# rm.net
KiCad netlist of a schematic drawn in EasyEDA Pro
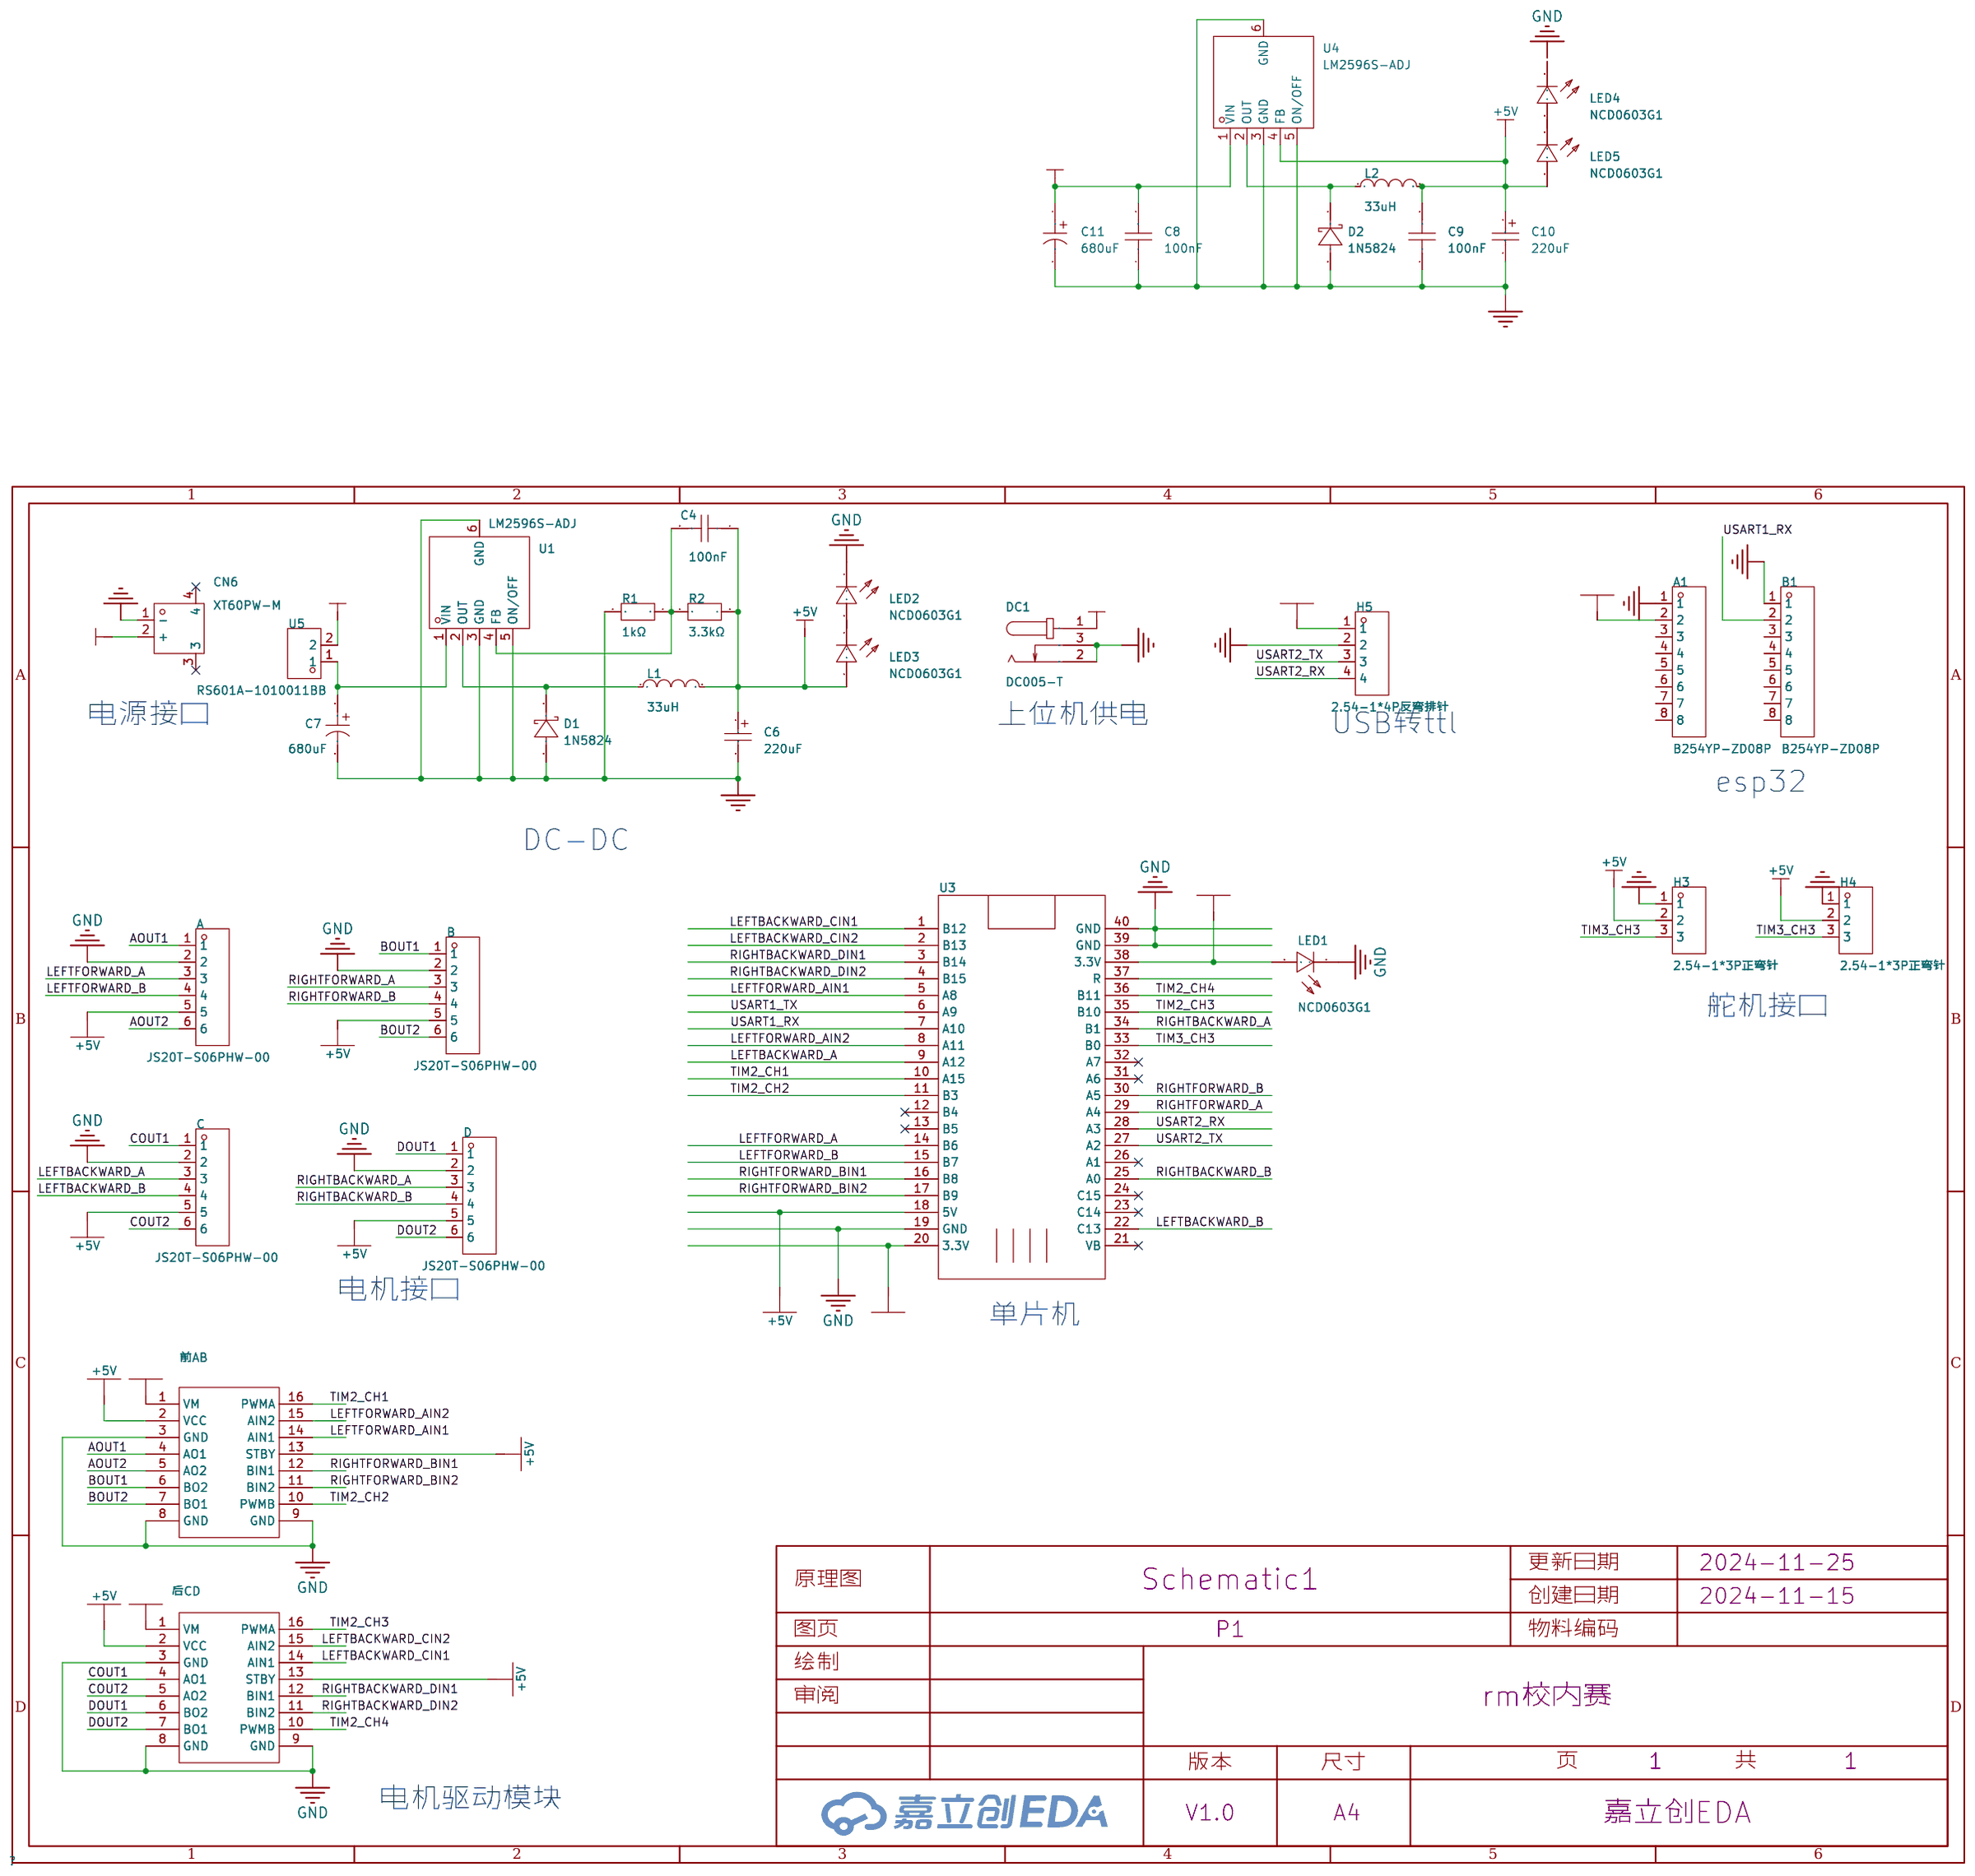
[diagram p0: schematic sheet]

(export (version "E")
  (design (tool "Eeschema 10.0.6"))
  (components
    (comp (ref "A")
      (value "JS20T-S06PHW-00")
      (footprint "easyedapro:CONN-TH_6P-P2.00_JS20T-S06PHW-00")
      (description "插针结构:1x6P;间距:2mm;安装方式:弯插;参考系列:PH;总PIN数:6P;排数:1;每排PIN数:6;触头材质:黄铜;")
      (fields (field (name "Manufacturer") "JS(钜硕电子)"))
      (libsource (lib "easyedapro") (part "JS20T-S06PHW-00"))
    )
    (comp (ref "A1")
      (value "B254YP-ZD08P")
      (footprint "easyedapro:HDR-TH_8P-P2.54-V-F")
      (fields (field (name "Manufacturer") "BXCONN(宝讯)"))
      (libsource (lib "easyedapro") (part "B254YP-ZD08P"))
    )
    (comp (ref "B")
      (value "JS20T-S06PHW-00")
      (footprint "easyedapro:CONN-TH_6P-P2.00_JS20T-S06PHW-00")
      (description "插针结构:1x6P;间距:2mm;安装方式:弯插;参考系列:PH;总PIN数:6P;排数:1;每排PIN数:6;触头材质:黄铜;")
      (fields (field (name "Manufacturer") "JS(钜硕电子)"))
      (libsource (lib "easyedapro") (part "JS20T-S06PHW-00"))
    )
    (comp (ref "B1")
      (value "B254YP-ZD08P")
      (footprint "easyedapro:HDR-TH_8P-P2.54-V-F")
      (fields (field (name "Manufacturer") "BXCONN(宝讯)"))
      (libsource (lib "easyedapro") (part "B254YP-ZD08P"))
    )
    (comp (ref "C")
      (value "JS20T-S06PHW-00")
      (footprint "easyedapro:CONN-TH_6P-P2.00_JS20T-S06PHW-00")
      (description "插针结构:1x6P;间距:2mm;安装方式:弯插;参考系列:PH;总PIN数:6P;排数:1;每排PIN数:6;触头材质:黄铜;")
      (fields (field (name "Manufacturer") "JS(钜硕电子)"))
      (libsource (lib "easyedapro") (part "JS20T-S06PHW-00"))
    )
    (comp (ref "C4")
      (value "100nF")
      (footprint "easyedapro:C0603")
      (description "容值:100nF;精度:±10%;额定电压:50V;材质(温度系数):X8L;")
      (fields (field (name "Manufacturer Part") "06035L104K4T2A") (field (name "Manufacturer") "Kyocera AVX"))
      (libsource (lib "easyedapro") (part "06035L104K4T2A"))
    )
    (comp (ref "C6")
      (value "220uF")
      (footprint "easyedapro:CASE-B_3528")
      (description "容值:220uF;精度:±20%;额定电压:6.3V;等效串联电阻:500mΩ@100kHz;")
      (fields
        (field (name "Manufacturer Part") "TLJB227M006R0500")
        (field (name "Manufacturer") "Kyocera AVX")
      )
      (libsource (lib "easyedapro") (part "TLJB227M006R0500"))
    )
    (comp (ref "C7")
      (value "680uF")
      (footprint "easyedapro:CAP-SMD_BD10.0-L10.3-W10.3-LS10.9-FD")
      (description "容值:680uF;精度:±20%;额定电压:35V;纹波电流:1.19A@120Hz;等效串联电阻:60mΩ@120Hz;")
      (fields (field (name "Manufacturer Part") "GVM1V681M1010") (field (name "Manufacturer") "HONOR(荣誉)"))
      (libsource (lib "easyedapro") (part "GVM1V681M1010"))
    )
    (comp (ref "C8")
      (value "100nF")
      (footprint "easyedapro:C0603")
      (description "容值:100nF;精度:±10%;额定电压:50V;材质(温度系数):X8L;")
      (fields (field (name "Manufacturer Part") "06035L104K4T2A") (field (name "Manufacturer") "Kyocera AVX"))
      (libsource (lib "easyedapro") (part "06035L104K4T2A"))
    )
    (comp (ref "C9")
      (value "100nF")
      (footprint "easyedapro:C0603")
      (description "容值:100nF;精度:±10%;额定电压:50V;材质(温度系数):X8L;")
      (fields (field (name "Manufacturer Part") "06035L104K4T2A") (field (name "Manufacturer") "Kyocera AVX"))
      (libsource (lib "easyedapro") (part "06035L104K4T2A"))
    )
    (comp (ref "C10")
      (value "220uF")
      (footprint "easyedapro:CASE-B_3528")
      (description "容值:220uF;精度:±20%;额定电压:6.3V;等效串联电阻:500mΩ@100kHz;")
      (fields
        (field (name "Manufacturer Part") "TLJB227M006R0500")
        (field (name "Manufacturer") "Kyocera AVX")
      )
      (libsource (lib "easyedapro") (part "TLJB227M006R0500"))
    )
    (comp (ref "C11")
      (value "680uF")
      (footprint "easyedapro:CAP-SMD_BD10.0-L10.3-W10.3-LS10.9-FD")
      (description "容值:680uF;精度:±20%;额定电压:35V;纹波电流:1.19A@120Hz;等效串联电阻:60mΩ@120Hz;")
      (fields (field (name "Manufacturer Part") "GVM1V681M1010") (field (name "Manufacturer") "HONOR(荣誉)"))
      (libsource (lib "easyedapro") (part "GVM1V681M1010"))
    )
    (comp (ref "CN6")
      (value "XT60PW-M")
      (footprint "easyedapro:CONN-TH_XT60PW-M")
      (description "类别:-;类型1:-;")
      (fields (field (name "Manufacturer") "AMASS(艾迈斯)"))
      (libsource (lib "easyedapro") (part "XT60PW-M"))
    )
    (comp (ref "D")
      (value "JS20T-S06PHW-00")
      (footprint "easyedapro:CONN-TH_6P-P2.00_JS20T-S06PHW-00")
      (description "插针结构:1x6P;间距:2mm;安装方式:弯插;参考系列:PH;总PIN数:6P;排数:1;每排PIN数:6;触头材质:黄铜;")
      (fields (field (name "Manufacturer") "JS(钜硕电子)"))
      (libsource (lib "easyedapro") (part "JS20T-S06PHW-00"))
    )
    (comp (ref "D1")
      (value "1N5824")
      (footprint "easyedapro:DO-27_BD5.3-L8.4-P12.40-D1.3-RD")
      (description "二极管配置:独立式;正向压降(Vf):550mV@5A;直流反向耐压(Vr):30V;平均整流电流(Io):5A;")
      (fields (field (name "Manufacturer") "FUXINSEMI(富芯森美)"))
      (libsource (lib "easyedapro") (part "1N5824_C7503125"))
    )
    (comp (ref "D2")
      (value "1N5824")
      (footprint "easyedapro:DO-27_BD5.3-L8.4-P12.40-D1.3-RD")
      (description "二极管配置:独立式;正向压降(Vf):550mV@5A;直流反向耐压(Vr):30V;平均整流电流(Io):5A;")
      (fields (field (name "Manufacturer") "FUXINSEMI(富芯森美)"))
      (libsource (lib "easyedapro") (part "1N5824_C7503125"))
    )
    (comp (ref "DC1")
      (value "DC005-T")
      (footprint "easyedapro:DC-IN-TH_DC005-T")
      (description "连接器类型:DC电源插座;安装方式:弯插;触点内径:2mm;触点外径:6.3mm;额定电流:500mA;额定电压:30V;工作温度范围:-40°C~+55°C;")
      (fields (field (name "Manufacturer") "SHOU HAN(首韩)"))
      (libsource (lib "easyedapro") (part "DC005-T"))
    )
    (comp (ref "H3")
      (value "2.54-1*3P正弯针")
      (footprint "easyedapro:HDR-TH_3P-P2.54-H-M-BW7.2-P")
      (fields (field (name "Manufacturer") "BOOMELE(博穆精密)"))
      (libsource (lib "easyedapro") (part "C92159"))
    )
    (comp (ref "H4")
      (value "2.54-1*3P正弯针")
      (footprint "easyedapro:HDR-TH_3P-P2.54-H-M-BW7.2-P")
      (fields (field (name "Manufacturer") "BOOMELE(博穆精密)"))
      (libsource (lib "easyedapro") (part "C92159"))
    )
    (comp (ref "H5")
      (value "2.54-1*4P反弯排针")
      (footprint "easyedapro:HDR-TH_4P-P2.54-H-M-W10.4")
      (fields (field (name "Manufacturer") "BOOMELE(博穆精密)"))
      (libsource (lib "easyedapro") (part "2.54-1*4P反弯排针"))
    )
    (comp (ref "L1")
      (value "33uH")
      (footprint "easyedapro:IND-SMD_L7.0-W6.6_FXL0630")
      (description "电感值:33uH;精度:±20%;额定电流:2A;饱和电流(Isat):2.5A;类型:一体成型电感;")
      (fields (field (name "Manufacturer Part") "FXL0630-330-M") (field (name "Manufacturer") "cjiang(长江微电)"))
      (libsource (lib "easyedapro") (part "FXL0630-330-M"))
    )
    (comp (ref "L2")
      (value "33uH")
      (footprint "easyedapro:IND-SMD_L7.0-W6.6_FXL0630")
      (description "电感值:33uH;精度:±20%;额定电流:2A;饱和电流(Isat):2.5A;类型:一体成型电感;")
      (fields (field (name "Manufacturer Part") "FXL0630-330-M") (field (name "Manufacturer") "cjiang(长江微电)"))
      (libsource (lib "easyedapro") (part "FXL0630-330-M"))
    )
    (comp (ref "LED1")
      (value "NCD0603G1")
      (footprint "easyedapro:LED0603-RD_1")
      (fields (field (name "Manufacturer") "国星光电"))
      (libsource (lib "easyedapro") (part "FC-D1608UGK-520D10"))
    )
    (comp (ref "LED2")
      (value "NCD0603G1")
      (footprint "easyedapro:LED0603-RD_1")
      (fields (field (name "Manufacturer") "国星光电"))
      (libsource (lib "easyedapro") (part "FC-D1608UGK-520D10"))
    )
    (comp (ref "LED3")
      (value "NCD0603G1")
      (footprint "easyedapro:LED0603-RD_1")
      (fields (field (name "Manufacturer") "国星光电"))
      (libsource (lib "easyedapro") (part "FC-D1608UGK-520D10"))
    )
    (comp (ref "LED4")
      (value "NCD0603G1")
      (footprint "easyedapro:LED0603-RD_1")
      (fields (field (name "Manufacturer") "国星光电"))
      (libsource (lib "easyedapro") (part "FC-D1608UGK-520D10"))
    )
    (comp (ref "LED5")
      (value "NCD0603G1")
      (footprint "easyedapro:LED0603-RD_1")
      (fields (field (name "Manufacturer") "国星光电"))
      (libsource (lib "easyedapro") (part "FC-D1608UGK-520D10"))
    )
    (comp (ref "R1")
      (value "1kΩ")
      (footprint "easyedapro:R0603")
      (description "电阻类型:厚膜电阻;阻值:10kΩ;精度:±5%;功率:100mW;最大工作电压:75V;温度系数:±100ppm/°C;")
      (fields (field (name "Manufacturer Part") "FRC0603J103TS") (field (name "Manufacturer") "FOJAN(富捷)"))
      (libsource (lib "easyedapro") (part "FRC0603J103TS"))
    )
    (comp (ref "R2")
      (value "3.3kΩ")
      (footprint "easyedapro:R0603")
      (description "电阻类型:厚膜电阻;阻值:10kΩ;精度:±5%;功率:100mW;最大工作电压:75V;温度系数:±100ppm/°C;")
      (fields (field (name "Manufacturer Part") "FRC0603J103TS") (field (name "Manufacturer") "FOJAN(富捷)"))
      (libsource (lib "easyedapro") (part "FRC0603J103TS"))
    )
    (comp (ref "U1")
      (value "LM2596S-ADJ")
      (footprint "easyedapro:TO-263-5_L10.0-W8.4-P1.70-LS15.3-BR")
      (description "功能类型:降压型;输出类型:可调;输入电压:40V;输出电压:1.23V~37V;输出电流(最大值):3.5A;")
      (fields (field (name "Manufacturer") "HXY MOSFET(华轩阳电子)"))
      (libsource (lib "easyedapro") (part "LM2596S-ADJ_C5349987"))
    )
    (comp (ref "U3") (value "~") (libsource (lib "easyedapro") (part "STM32F103C8T6核心板")))
    (comp (ref "U4")
      (value "LM2596S-ADJ")
      (footprint "easyedapro:TO-263-5_L10.0-W8.4-P1.70-LS15.3-BR")
      (description "功能类型:降压型;输出类型:可调;输入电压:40V;输出电压:1.23V~37V;输出电流(最大值):3.5A;")
      (fields (field (name "Manufacturer") "HXY MOSFET(华轩阳电子)"))
      (libsource (lib "easyedapro") (part "LM2596S-ADJ_C5349987"))
    )
    (comp (ref "U5")
      (value "RS601A-1010011BB")
      (footprint "easyedapro:SW-TH_RS601A-1010011BB")
      (description "带灯:无;引脚样式:焊片;额定电流:6A;额定电压(AC):250V;额定电压(DC):-;电路结构:单刀单掷;机械寿命:1万次;")
      (fields (field (name "Manufacturer") "HCTL(华灿天禄)"))
      (libsource (lib "easyedapro") (part "RS601A-1010011BB_C2885779"))
    )
    (comp (ref "前AB") (value "~") (libsource (lib "easyedapro") (part "TB6612FNG模块")))
    (comp (ref "后CD") (value "~") (libsource (lib "easyedapro") (part "TB6612FNG模块")))
  )
  (nets
    (net (code "1") (name "+3.3V") (class "Default")
      (node (ref "A1") (pin "2") (pinfunction "2_2") (pintype "unspecified"))
      (node (ref "H5") (pin "1") (pinfunction "1_1") (pintype "unspecified"))
      (node (ref "LED1") (pin "2") (pinfunction "A_2") (pintype "input"))
      (node (ref "U3") (pin "20") (pinfunction "3.3V_20") (pintype "unspecified"))
      (node (ref "U3") (pin "38") (pinfunction "3.3V_38") (pintype "unspecified"))
    )
    (net (code "2") (name "+5V") (class "Default")
      (node (ref "A") (pin "5") (pinfunction "5_5") (pintype "unspecified"))
      (node (ref "B") (pin "5") (pinfunction "5_5") (pintype "unspecified"))
      (node (ref "C") (pin "5") (pinfunction "5_5") (pintype "unspecified"))
      (node (ref "C10") (pin "1") (pinfunction "1_1") (pintype "input"))
      (node (ref "C4") (pin "1") (pinfunction "1_1") (pintype "unspecified"))
      (node (ref "C6") (pin "1") (pinfunction "1_1") (pintype "input"))
      (node (ref "C9") (pin "2") (pinfunction "2_2") (pintype "unspecified"))
      (node (ref "D") (pin "5") (pinfunction "5_5") (pintype "unspecified"))
      (node (ref "H3") (pin "2") (pinfunction "2_2") (pintype "unspecified"))
      (node (ref "H4") (pin "2") (pinfunction "2_2") (pintype "unspecified"))
      (node (ref "L1") (pin "2") (pinfunction "2_2") (pintype "unspecified"))
      (node (ref "L2") (pin "2") (pinfunction "2_2") (pintype "unspecified"))
      (node (ref "LED3") (pin "2") (pinfunction "A_2") (pintype "input"))
      (node (ref "LED5") (pin "2") (pinfunction "A_2") (pintype "input"))
      (node (ref "R2") (pin "2") (pinfunction "2_2") (pintype "unspecified"))
      (node (ref "U3") (pin "18") (pinfunction "5V_18") (pintype "unspecified"))
      (node (ref "U4") (pin "4") (pinfunction "FB_4") (pintype "unspecified"))
      (node (ref "前AB") (pin "13") (pinfunction "STBY_13") (pintype "input"))
      (node (ref "前AB") (pin "2") (pinfunction "VCC_2") (pintype "input"))
      (node (ref "后CD") (pin "13") (pinfunction "STBY_13") (pintype "input"))
      (node (ref "后CD") (pin "2") (pinfunction "VCC_2") (pintype "input"))
    )
    (net (code "3") (name "+12V") (class "Default")
      (node (ref "C11") (pin "1") (pinfunction "1_1") (pintype "input"))
      (node (ref "C8") (pin "2") (pinfunction "2_2") (pintype "unspecified"))
      (node (ref "CN6") (pin "2") (pinfunction "+_2") (pintype "unspecified"))
      (node (ref "DC1") (pin "1") (pinfunction "1_1") (pintype "unspecified"))
      (node (ref "U4") (pin "1") (pinfunction "VIN_1") (pintype "unspecified"))
      (node (ref "前AB") (pin "1") (pinfunction "VM_1") (pintype "input"))
      (node (ref "后CD") (pin "1") (pinfunction "VM_1") (pintype "input"))
    )
    (net (code "4") (name "+12VIN") (class "Default")
      (node (ref "U5") (pin "2") (pinfunction "2_2") (pintype "unspecified"))
    )
    (net (code "5") (name "/AOUT1") (class "Default")
      (node (ref "A") (pin "1") (pinfunction "1_1") (pintype "unspecified"))
      (node (ref "前AB") (pin "4") (pinfunction "AO1_4") (pintype "input"))
    )
    (net (code "6") (name "/AOUT2") (class "Default")
      (node (ref "A") (pin "6") (pinfunction "6_6") (pintype "unspecified"))
      (node (ref "前AB") (pin "5") (pinfunction "AO2_5") (pintype "input"))
    )
    (net (code "7") (name "/BOUT1") (class "Default")
      (node (ref "B") (pin "1") (pinfunction "1_1") (pintype "unspecified"))
      (node (ref "前AB") (pin "6") (pinfunction "BO2_6") (pintype "input"))
    )
    (net (code "8") (name "/BOUT2") (class "Default")
      (node (ref "B") (pin "6") (pinfunction "6_6") (pintype "unspecified"))
      (node (ref "前AB") (pin "7") (pinfunction "BO1_7") (pintype "input"))
    )
    (net (code "9") (name "/COUT1") (class "Default")
      (node (ref "C") (pin "1") (pinfunction "1_1") (pintype "unspecified"))
      (node (ref "后CD") (pin "4") (pinfunction "AO1_4") (pintype "input"))
    )
    (net (code "10") (name "/COUT2") (class "Default")
      (node (ref "C") (pin "6") (pinfunction "6_6") (pintype "unspecified"))
      (node (ref "后CD") (pin "5") (pinfunction "AO2_5") (pintype "input"))
    )
    (net (code "11") (name "/DOUT1") (class "Default")
      (node (ref "D") (pin "1") (pinfunction "1_1") (pintype "unspecified"))
      (node (ref "后CD") (pin "6") (pinfunction "BO2_6") (pintype "input"))
    )
    (net (code "12") (name "/DOUT2") (class "Default")
      (node (ref "D") (pin "6") (pinfunction "6_6") (pintype "unspecified"))
      (node (ref "后CD") (pin "7") (pinfunction "BO1_7") (pintype "input"))
    )
    (net (code "13") (name "/LEFTBACKWARD_A") (class "Default")
      (node (ref "C") (pin "3") (pinfunction "3_3") (pintype "unspecified"))
      (node (ref "U3") (pin "9") (pinfunction "A12_9") (pintype "unspecified"))
    )
    (net (code "14") (name "/LEFTBACKWARD_B") (class "Default")
      (node (ref "C") (pin "4") (pinfunction "4_4") (pintype "unspecified"))
      (node (ref "U3") (pin "22") (pinfunction "C13_22") (pintype "unspecified"))
    )
    (net (code "15") (name "/LEFTBACKWARD_CIN1") (class "Default")
      (node (ref "U3") (pin "1") (pinfunction "B12_1") (pintype "unspecified"))
      (node (ref "后CD") (pin "14") (pinfunction "AIN1_14") (pintype "input"))
    )
    (net (code "16") (name "/LEFTBACKWARD_CIN2") (class "Default")
      (node (ref "U3") (pin "2") (pinfunction "B13_2") (pintype "unspecified"))
      (node (ref "后CD") (pin "15") (pinfunction "AIN2_15") (pintype "input"))
    )
    (net (code "17") (name "/LEFTFORWARD_A") (class "Default")
      (node (ref "A") (pin "3") (pinfunction "3_3") (pintype "unspecified"))
      (node (ref "U3") (pin "14") (pinfunction "B6_14") (pintype "unspecified"))
    )
    (net (code "18") (name "/LEFTFORWARD_AIN1") (class "Default")
      (node (ref "U3") (pin "5") (pinfunction "A8_5") (pintype "unspecified"))
      (node (ref "前AB") (pin "14") (pinfunction "AIN1_14") (pintype "input"))
    )
    (net (code "19") (name "/LEFTFORWARD_AIN2") (class "Default")
      (node (ref "U3") (pin "8") (pinfunction "A11_8") (pintype "unspecified"))
      (node (ref "前AB") (pin "15") (pinfunction "AIN2_15") (pintype "input"))
    )
    (net (code "20") (name "/LEFTFORWARD_B") (class "Default")
      (node (ref "A") (pin "4") (pinfunction "4_4") (pintype "unspecified"))
      (node (ref "U3") (pin "15") (pinfunction "B7_15") (pintype "unspecified"))
    )
    (net (code "21") (name "/RIGHTBACKWARD_A") (class "Default")
      (node (ref "D") (pin "3") (pinfunction "3_3") (pintype "unspecified"))
      (node (ref "U3") (pin "34") (pinfunction "B1_34") (pintype "unspecified"))
    )
    (net (code "22") (name "/RIGHTBACKWARD_B") (class "Default")
      (node (ref "D") (pin "4") (pinfunction "4_4") (pintype "unspecified"))
      (node (ref "U3") (pin "25") (pinfunction "A0_25") (pintype "unspecified"))
    )
    (net (code "23") (name "/RIGHTBACKWARD_DIN1") (class "Default")
      (node (ref "U3") (pin "3") (pinfunction "B14_3") (pintype "unspecified"))
      (node (ref "后CD") (pin "12") (pinfunction "BIN1_12") (pintype "input"))
    )
    (net (code "24") (name "/RIGHTBACKWARD_DIN2") (class "Default")
      (node (ref "U3") (pin "4") (pinfunction "B15_4") (pintype "unspecified"))
      (node (ref "后CD") (pin "11") (pinfunction "BIN2_11") (pintype "input"))
    )
    (net (code "25") (name "/RIGHTFORWARD_A") (class "Default")
      (node (ref "B") (pin "3") (pinfunction "3_3") (pintype "unspecified"))
      (node (ref "U3") (pin "29") (pinfunction "A4_29") (pintype "unspecified"))
    )
    (net (code "26") (name "/RIGHTFORWARD_B") (class "Default")
      (node (ref "B") (pin "4") (pinfunction "4_4") (pintype "unspecified"))
      (node (ref "U3") (pin "30") (pinfunction "A5_30") (pintype "unspecified"))
    )
    (net (code "27") (name "/RIGHTFORWARD_BIN1") (class "Default")
      (node (ref "U3") (pin "16") (pinfunction "B8_16") (pintype "unspecified"))
      (node (ref "前AB") (pin "12") (pinfunction "BIN1_12") (pintype "input"))
    )
    (net (code "28") (name "/RIGHTFORWARD_BIN2") (class "Default")
      (node (ref "U3") (pin "17") (pinfunction "B9_17") (pintype "unspecified"))
      (node (ref "前AB") (pin "11") (pinfunction "BIN2_11") (pintype "input"))
    )
    (net (code "29") (name "/TIM2_CH1") (class "Default")
      (node (ref "U3") (pin "10") (pinfunction "A15_10") (pintype "unspecified"))
      (node (ref "前AB") (pin "16") (pinfunction "PWMA_16") (pintype "input"))
    )
    (net (code "30") (name "/TIM2_CH2") (class "Default")
      (node (ref "U3") (pin "11") (pinfunction "B3_11") (pintype "unspecified"))
      (node (ref "前AB") (pin "10") (pinfunction "PWMB_10") (pintype "input"))
    )
    (net (code "31") (name "/TIM2_CH3") (class "Default")
      (node (ref "U3") (pin "35") (pinfunction "B10_35") (pintype "unspecified"))
      (node (ref "后CD") (pin "16") (pinfunction "PWMA_16") (pintype "input"))
    )
    (net (code "32") (name "/TIM2_CH4") (class "Default")
      (node (ref "U3") (pin "36") (pinfunction "B11_36") (pintype "unspecified"))
      (node (ref "后CD") (pin "10") (pinfunction "PWMB_10") (pintype "input"))
    )
    (net (code "33") (name "/TIM3_CH3") (class "Default")
      (node (ref "H3") (pin "3") (pinfunction "3_3") (pintype "unspecified"))
      (node (ref "H4") (pin "3") (pinfunction "3_3") (pintype "unspecified"))
      (node (ref "U3") (pin "33") (pinfunction "B0_33") (pintype "unspecified"))
    )
    (net (code "34") (name "/USART1_RX") (class "Default")
      (node (ref "B1") (pin "2") (pinfunction "2_2") (pintype "unspecified"))
      (node (ref "U3") (pin "7") (pinfunction "A10_7") (pintype "unspecified"))
    )
    (net (code "35") (name "/USART1_TX") (class "Default")
      (node (ref "U3") (pin "6") (pinfunction "A9_6") (pintype "unspecified"))
    )
    (net (code "36") (name "/USART2_RX") (class "Default")
      (node (ref "H5") (pin "4") (pinfunction "4_4") (pintype "unspecified"))
      (node (ref "U3") (pin "28") (pinfunction "A3_28") (pintype "unspecified"))
    )
    (net (code "37") (name "/USART2_TX") (class "Default")
      (node (ref "H5") (pin "3") (pinfunction "3_3") (pintype "unspecified"))
      (node (ref "U3") (pin "27") (pinfunction "A2_27") (pintype "unspecified"))
    )
    (net (code "38") (name "GND") (class "Default")
      (node (ref "A") (pin "2") (pinfunction "2_2") (pintype "unspecified"))
      (node (ref "A1") (pin "1") (pinfunction "1_1") (pintype "unspecified"))
      (node (ref "B") (pin "2") (pinfunction "2_2") (pintype "unspecified"))
      (node (ref "B1") (pin "1") (pinfunction "1_1") (pintype "unspecified"))
      (node (ref "C") (pin "2") (pinfunction "2_2") (pintype "unspecified"))
      (node (ref "C10") (pin "2") (pinfunction "2_2") (pintype "input"))
      (node (ref "C11") (pin "2") (pinfunction "2_2") (pintype "input"))
      (node (ref "C6") (pin "2") (pinfunction "2_2") (pintype "input"))
      (node (ref "C7") (pin "2") (pinfunction "2_2") (pintype "input"))
      (node (ref "C8") (pin "1") (pinfunction "1_1") (pintype "unspecified"))
      (node (ref "C9") (pin "1") (pinfunction "1_1") (pintype "unspecified"))
      (node (ref "CN6") (pin "1") (pinfunction "-_1") (pintype "unspecified"))
      (node (ref "D") (pin "2") (pinfunction "2_2") (pintype "unspecified"))
      (node (ref "D1") (pin "2") (pinfunction "A_2") (pintype "unspecified"))
      (node (ref "D2") (pin "2") (pinfunction "A_2") (pintype "unspecified"))
      (node (ref "DC1") (pin "2") (pinfunction "2_2") (pintype "unspecified"))
      (node (ref "DC1") (pin "3") (pinfunction "3_3") (pintype "unspecified"))
      (node (ref "H3") (pin "1") (pinfunction "1_1") (pintype "unspecified"))
      (node (ref "H4") (pin "1") (pinfunction "1_1") (pintype "unspecified"))
      (node (ref "H5") (pin "2") (pinfunction "2_2") (pintype "unspecified"))
      (node (ref "LED1") (pin "1") (pinfunction "K_1") (pintype "input"))
      (node (ref "LED2") (pin "1") (pinfunction "K_1") (pintype "input"))
      (node (ref "R1") (pin "2") (pinfunction "2_2") (pintype "unspecified"))
      (node (ref "U1") (pin "3") (pinfunction "GND_3") (pintype "unspecified"))
      (node (ref "U1") (pin "5") (pinfunction "ON/OFF_5") (pintype "unspecified"))
      (node (ref "U1") (pin "6") (pinfunction "GND_6") (pintype "unspecified"))
      (node (ref "U3") (pin "19") (pinfunction "GND_19") (pintype "unspecified"))
      (node (ref "U3") (pin "39") (pinfunction "GND_39") (pintype "unspecified"))
      (node (ref "U3") (pin "40") (pinfunction "GND_40") (pintype "unspecified"))
      (node (ref "U4") (pin "3") (pinfunction "GND_3") (pintype "unspecified"))
      (node (ref "U4") (pin "5") (pinfunction "ON/OFF_5") (pintype "unspecified"))
      (node (ref "U4") (pin "6") (pinfunction "GND_6") (pintype "unspecified"))
      (node (ref "前AB") (pin "3") (pinfunction "GND_3") (pintype "input"))
      (node (ref "前AB") (pin "8") (pinfunction "GND_8") (pintype "input"))
      (node (ref "前AB") (pin "9") (pinfunction "GND_9") (pintype "input"))
      (node (ref "后CD") (pin "3") (pinfunction "GND_3") (pintype "input"))
      (node (ref "后CD") (pin "8") (pinfunction "GND_8") (pintype "input"))
      (node (ref "后CD") (pin "9") (pinfunction "GND_9") (pintype "input"))
    )
    (net (code "39") (name "Net-(D1-K)") (class "Default")
      (node (ref "D1") (pin "1") (pinfunction "K_1") (pintype "unspecified"))
      (node (ref "L1") (pin "1") (pinfunction "1_1") (pintype "unspecified"))
      (node (ref "U1") (pin "2") (pinfunction "OUT_2") (pintype "unspecified"))
    )
    (net (code "40") (name "Net-(D2-K)") (class "Default")
      (node (ref "D2") (pin "1") (pinfunction "K_1") (pintype "unspecified"))
      (node (ref "L2") (pin "1") (pinfunction "1_1") (pintype "unspecified"))
      (node (ref "U4") (pin "2") (pinfunction "OUT_2") (pintype "unspecified"))
    )
    (net (code "41") (name "Net-(LED2-A)") (class "Default")
      (node (ref "LED2") (pin "2") (pinfunction "A_2") (pintype "input"))
      (node (ref "LED3") (pin "1") (pinfunction "K_1") (pintype "input"))
    )
    (net (code "42") (name "Net-(LED4-A)") (class "Default")
      (node (ref "LED4") (pin "2") (pinfunction "A_2") (pintype "input"))
      (node (ref "LED5") (pin "1") (pinfunction "K_1") (pintype "input"))
    )
    (net (code "43") (name "Net-(U1-FB)") (class "Default")
      (node (ref "C4") (pin "2") (pinfunction "2_2") (pintype "unspecified"))
      (node (ref "R1") (pin "1") (pinfunction "1_1") (pintype "unspecified"))
      (node (ref "R2") (pin "1") (pinfunction "1_1") (pintype "unspecified"))
      (node (ref "U1") (pin "4") (pinfunction "FB_4") (pintype "unspecified"))
    )
    (net (code "44") (name "Net-(U1-VIN)") (class "Default")
      (node (ref "C7") (pin "1") (pinfunction "1_1") (pintype "input"))
      (node (ref "U1") (pin "1") (pinfunction "VIN_1") (pintype "unspecified"))
      (node (ref "U5") (pin "1") (pinfunction "1_1") (pintype "unspecified"))
    )
    (net (code "45") (name "unconnected-(A1-Pad3)") (class "Default")
      (node (ref "A1") (pin "3") (pinfunction "3_3") (pintype "unspecified"))
    )
    (net (code "46") (name "unconnected-(A1-Pad4)") (class "Default")
      (node (ref "A1") (pin "4") (pinfunction "4_4") (pintype "unspecified"))
    )
    (net (code "47") (name "unconnected-(A1-Pad5)") (class "Default")
      (node (ref "A1") (pin "5") (pinfunction "5_5") (pintype "unspecified"))
    )
    (net (code "48") (name "unconnected-(A1-Pad6)") (class "Default")
      (node (ref "A1") (pin "6") (pinfunction "6_6") (pintype "unspecified"))
    )
    (net (code "49") (name "unconnected-(A1-Pad7)") (class "Default")
      (node (ref "A1") (pin "7") (pinfunction "7_7") (pintype "unspecified"))
    )
    (net (code "50") (name "unconnected-(A1-Pad8)") (class "Default")
      (node (ref "A1") (pin "8") (pinfunction "8_8") (pintype "unspecified"))
    )
    (net (code "51") (name "unconnected-(B1-Pad3)") (class "Default")
      (node (ref "B1") (pin "3") (pinfunction "3_3") (pintype "unspecified"))
    )
    (net (code "52") (name "unconnected-(B1-Pad4)") (class "Default")
      (node (ref "B1") (pin "4") (pinfunction "4_4") (pintype "unspecified"))
    )
    (net (code "53") (name "unconnected-(B1-Pad5)") (class "Default")
      (node (ref "B1") (pin "5") (pinfunction "5_5") (pintype "unspecified"))
    )
    (net (code "54") (name "unconnected-(B1-Pad6)") (class "Default")
      (node (ref "B1") (pin "6") (pinfunction "6_6") (pintype "unspecified"))
    )
    (net (code "55") (name "unconnected-(B1-Pad7)") (class "Default")
      (node (ref "B1") (pin "7") (pinfunction "7_7") (pintype "unspecified"))
    )
    (net (code "56") (name "unconnected-(B1-Pad8)") (class "Default")
      (node (ref "B1") (pin "8") (pinfunction "8_8") (pintype "unspecified"))
    )
    (net (code "57") (name "unconnected-(CN6-Pad3)") (class "Default")
      (node (ref "CN6") (pin "3") (pinfunction "3_3") (pintype "unspecified+no_connect"))
    )
    (net (code "58") (name "unconnected-(CN6-Pad4)") (class "Default")
      (node (ref "CN6") (pin "4") (pinfunction "4_4") (pintype "unspecified+no_connect"))
    )
    (net (code "59") (name "unconnected-(LED4-K-Pad1)") (class "Default")
      (node (ref "LED4") (pin "1") (pinfunction "K_1") (pintype "input"))
    )
    (net (code "60") (name "unconnected-(U3-A1-Pad26)") (class "Default")
      (node (ref "U3") (pin "26") (pinfunction "A1_26") (pintype "unspecified+no_connect"))
    )
    (net (code "61") (name "unconnected-(U3-A6-Pad31)") (class "Default")
      (node (ref "U3") (pin "31") (pinfunction "A6_31") (pintype "unspecified+no_connect"))
    )
    (net (code "62") (name "unconnected-(U3-A7-Pad32)") (class "Default")
      (node (ref "U3") (pin "32") (pinfunction "A7_32") (pintype "unspecified+no_connect"))
    )
    (net (code "63") (name "unconnected-(U3-B4-Pad12)") (class "Default")
      (node (ref "U3") (pin "12") (pinfunction "B4_12") (pintype "unspecified+no_connect"))
    )
    (net (code "64") (name "unconnected-(U3-B5-Pad13)") (class "Default")
      (node (ref "U3") (pin "13") (pinfunction "B5_13") (pintype "unspecified+no_connect"))
    )
    (net (code "65") (name "unconnected-(U3-C14-Pad23)") (class "Default")
      (node (ref "U3") (pin "23") (pinfunction "C14_23") (pintype "unspecified+no_connect"))
    )
    (net (code "66") (name "unconnected-(U3-C15-Pad24)") (class "Default")
      (node (ref "U3") (pin "24") (pinfunction "C15_24") (pintype "unspecified+no_connect"))
    )
    (net (code "67") (name "unconnected-(U3-R-Pad37)") (class "Default")
      (node (ref "U3") (pin "37") (pinfunction "R_37") (pintype "unspecified"))
    )
    (net (code "68") (name "unconnected-(U3-VB-Pad21)") (class "Default")
      (node (ref "U3") (pin "21") (pinfunction "VB_21") (pintype "unspecified+no_connect"))
    )
  )
)
